# AdaptiveLightingSatellite.net
KiCad netlist of a schematic drawn in Altium Designer
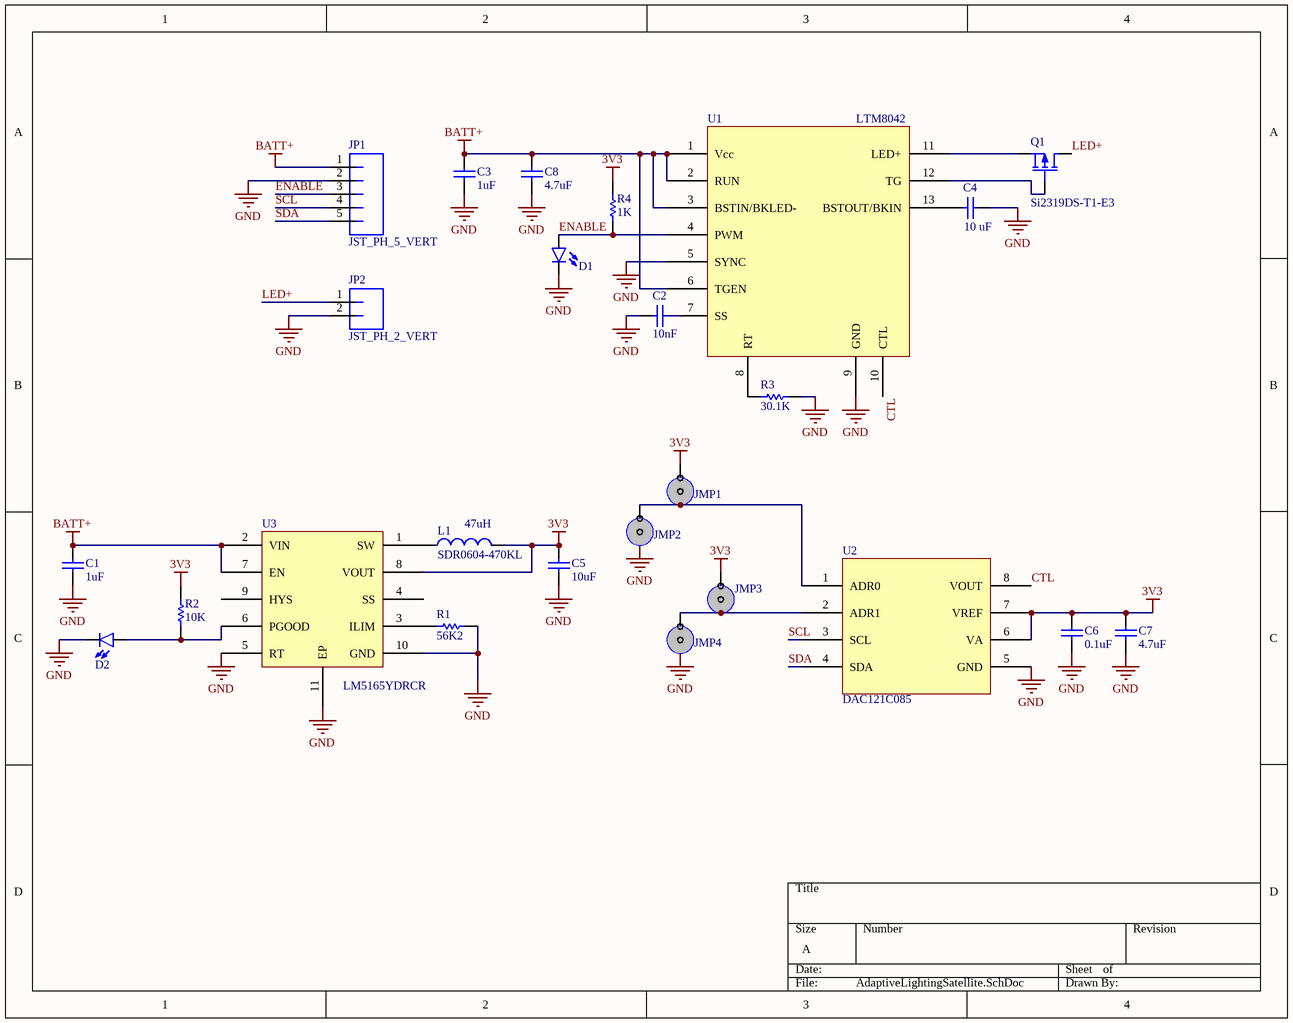
[diagram p0: AdaptiveLightingSatellite.SchDoc]

(export (version "E")
  (design (tool "Eeschema 10.0.6"))
  (components
    (comp (ref "C1")
      (value "1uF")
      (footprint "C0805[2012X120]")
      (description "CAP_1uF 50V 20% 0805 (2012 metric)")
      (fields (field (name "MANUFACTURER") "TDK") (field (name "PARTNUMBER") "C2012X5R1H105M085AB"))
      (libsource (lib "Capacitors") (part "CAP_1uF_100V_0805_20%"))
    )
    (comp (ref "C2")
      (value "10nF")
      (footprint "C0402[1005X55]")
      (description "10nF 100V 10% 0402 (1005 Metric)")
      (fields (field (name "PARTNUMBER") "C1005X7S2A103K050BB") (field (name "MANUFACTURER") "TDK"))
      (libsource (lib "Capacitors") (part "CAP_10nF_100V_0402_10%"))
    )
    (comp (ref "C3")
      (value "1uF")
      (footprint "C0805[2012X120]")
      (description "CAP_1uF 50V 20% 0805 (2012 metric)")
      (fields (field (name "MANUFACTURER") "TDK") (field (name "PARTNUMBER") "C2012X5R1H105M085AB"))
      (libsource (lib "Capacitors") (part "CAP_1uF_100V_0805_20%"))
    )
    (comp (ref "C4")
      (value "10 uF")
      (footprint "C1210[3225X150]")
      (description "10uF 50V X5R +/-20% 1210")
      (fields (field (name "VOLTAGE") "50V") (field (name "MANUFACTURER") "Taiyo Yuden"))
      (libsource (lib "Capacitors") (part "CAP_10uF_50V_1210_20%"))
    )
    (comp (ref "C5")
      (value "10uF")
      (footprint "C0402[1005X55]")
      (description "10uF 6.3V 20% 0402 (1005 Metric)")
      (fields (field (name "PARTNUMBER") "GRM155R60J106ME44D") (field (name "MANUFACTURER") "Murata"))
      (libsource (lib "Capacitors") (part "CAP_10uF_6.3V_0402_20%"))
    )
    (comp (ref "C6")
      (value "0.1uF")
      (footprint "C0402[1005X55]")
      (description "0.1uF 6.3V 10% 0402 (1005 Metric)")
      (fields (field (name "PARTNUMBER") "GRM155R70J104KA01D") (field (name "MANUFACTURER") "Murata"))
      (libsource (lib "Capacitors") (part "CAP_0.1uF_6.3V_0402_10%"))
    )
    (comp (ref "C7")
      (value "4.7uF")
      (footprint "C0402[1005X55]")
      (description "4.7uF 6.3V 20% 0402 (1005 Metric)")
      (fields (field (name "PARTNUMBER") "GRM155R60J475ME47D") (field (name "MANUFACTURER") "Murata"))
      (libsource (lib "Capacitors") (part "CAP_4.7uF_6.3V_0402_20%"))
    )
    (comp (ref "C8")
      (value "4.7uF")
      (footprint "C1210[3225X200]")
      (description "4.7uF 100V 10% 1210 (3225 Metric)")
      (fields (field (name "PARTNUMBER") "GRJ32DC72A475KE11L") (field (name "MANUFACTURER") "Murata"))
      (libsource (lib "Capacitors") (part "CAP_4.7uF_100V_1210_10%"))
    )
    (comp (ref "D1")
      (value "LED_0603_GREEN_5mA")
      (footprint "LED0603")
      (fields (field (name "PARTNUMBER") "LTST-C193TGKT-5A") (field (name "MANUFACTURER") "Lite-On Inc."))
      (libsource (lib "LEDs") (part "LED_0603_GREEN_5mA"))
    )
    (comp (ref "D2")
      (value "LED_0603_BLUE_5mA")
      (footprint "LED0603")
      (fields (field (name "PARTNUMBER") "LTST-C193TBKT-5A") (field (name "MANUFACTURER") "Lite-On Inc."))
      (libsource (lib "LEDs") (part "LED_0603_BLUE_5mA"))
    )
    (comp (ref "JMP1")
      (value "Solder Jumper")
      (footprint "SOLDER-JUMPER")
      (libsource (lib "Connectors") (part "SOLDER_JMPR"))
    )
    (comp (ref "JMP2")
      (value "Solder Jumper")
      (footprint "SOLDER-JUMPER")
      (libsource (lib "Connectors") (part "SOLDER_JMPR"))
    )
    (comp (ref "JMP3")
      (value "~")
      (footprint "SOLDER-JUMPER")
      (libsource (lib "Connectors") (part "SOLDER_JMPR"))
    )
    (comp (ref "JMP4")
      (value "Solder Jumper")
      (footprint "SOLDER-JUMPER")
      (libsource (lib "Connectors") (part "SOLDER_JMPR"))
    )
    (comp (ref "JP1")
      (value "JST_PH_5_VERT")
      (footprint "JST-PH-5-PTH-VERT")
      (fields
        (field (name "MANUFACTURER") "JST Sales America, Inc.")
        (field (name "PARTNUMBER") "B5B-PH-K-S(LF)(SN)")
      )
      (libsource (lib "Connectors") (part "JST_PH_5_VERT"))
    )
    (comp (ref "JP2")
      (value "JST_PH_2_VERT")
      (footprint "JST-PH-2-PTH-VERT")
      (fields
        (field (name "MANUFACTURER") "JST Sales America, Inc.")
        (field (name "PARTNUMBER") "B2B-PH-K-S(LF)(SN)")
      )
      (libsource (lib "Connectors") (part "JST_PH_2_VERT"))
    )
    (comp (ref "L1")
      (value "SDR0604-470KL")
      (footprint "SDR0604")
      (description "47uH 10% 0.72A 0604")
      (fields (field (name "MANUFACTURER") "Bourns") (field (name "ALTIUM_VALUE") "47uH"))
      (libsource (lib "Inductors") (part "SDR0604-470KL"))
    )
    (comp (ref "Q1")
      (value "Si2319DS-T1-E3")
      (footprint "SOT23-3")
      (description "P-Channel MOSFET")
      (fields (field (name "MANUFACTURER") "Vishay") (field (name "PARTNUMBER") "Si2319DS-T1-E3 #PBF"))
      (libsource (lib "MOSFETs") (part "Si2319DS-T1-E3"))
    )
    (comp (ref "R1")
      (value "56K2")
      (footprint "R0402[1005]")
      (description "56K2 0.063W 1% 0402 (1005 Metric)")
      (fields (field (name "MANUFACTURER") "KOA Speer") (field (name "PARTNUMBER") "RK73H1ETTP5622F"))
      (libsource (lib "Resistors") (part "RES_56K2_0402_1%"))
    )
    (comp (ref "R2")
      (value "10K")
      (footprint "R0402[1005]")
      (description "10K 0.063W 1% 0402 (1005 Metric)")
      (fields (field (name "MANUFACTURER") "KOA Speer") (field (name "PARTNUMBER") "RK73H1ETTP1002F"))
      (libsource (lib "Resistors") (part "RES_10K_0402_1%"))
    )
    (comp (ref "R3")
      (value "30.1K")
      (footprint "R0603[1608]")
      (description "30.1K 0.06W 1% 0603 (1005 Metric)")
      (fields (field (name "MANUFACTURER") "NIC Corporation") (field (name "PARTNUMBER") "NRC06F3012TRF"))
      (libsource (lib "Resistors") (part "RES_30.1K_0603_1%"))
    )
    (comp (ref "R4")
      (value "1K")
      (footprint "R0402[1005]")
      (description "1K 0.063W 1% 0402 (1005 Metric)")
      (fields (field (name "MANUFACTURER") "KOA Speer") (field (name "PARTNUMBER") "RK73H1ETTP1001F"))
      (libsource (lib "Resistors") (part "RES_1K_0402_1%"))
    )
    (comp (ref "U1")
      (value "LTM8042")
      (footprint "LGA-77")
      (fields (field (name "MANUFACTURER") "Linear Technology") (field (name "PARTNUMBER") "LTM8042EV#PBF"))
      (libsource (lib "ICs") (part "LTM8042"))
    )
    (comp (ref "U2")
      (value "DAC121C085")
      (footprint "TSSOP-8")
      (description "12 Bit Digital to Analog Converter")
      (fields (field (name "MANUFACTURER") "Texas Instruments"))
      (libsource (lib "ICs") (part "DAC121C085"))
    )
    (comp (ref "U3")
      (value "LM5165YDRCR")
      (footprint "VSON-10 (3mmx3mm)")
      (description "LM5165 3-V to 65-V Input, 150-mA Synchronous Buck Converter")
      (fields (field (name "MANUFACTURER") "Texas Instruments"))
      (libsource (lib "ICs") (part "LM5165YDRCR"))
    )
  )
  (nets
    (net (code "1") (name "/CTL") (class "Default")
      (node (ref "U1") (pin "10") (pinfunction "CTL_10") (pintype "passive"))
      (node (ref "U2") (pin "8") (pinfunction "VOUT_8") (pintype "passive"))
    )
    (net (code "2") (name "/ENABLE") (class "Default")
      (node (ref "D1") (pin "A") (pinfunction "A_A") (pintype "passive"))
      (node (ref "JP1") (pin "3") (pinfunction "3_3") (pintype "passive"))
      (node (ref "R4") (pin "1") (pinfunction "1_1") (pintype "passive"))
      (node (ref "U1") (pin "4") (pinfunction "PWM_4") (pintype "passive"))
    )
    (net (code "3") (name "/LED+") (class "Default")
      (node (ref "JP2") (pin "1") (pinfunction "1_1") (pintype "passive"))
      (node (ref "Q1") (pin "2") (pinfunction "D_2") (pintype "passive"))
    )
    (net (code "4") (name "/SCL") (class "Default")
      (node (ref "JP1") (pin "4") (pinfunction "4_4") (pintype "passive"))
      (node (ref "U2") (pin "3") (pinfunction "SCL_3") (pintype "passive"))
    )
    (net (code "5") (name "/SDA") (class "Default")
      (node (ref "JP1") (pin "5") (pinfunction "5_5") (pintype "passive"))
      (node (ref "U2") (pin "4") (pinfunction "SDA_4") (pintype "passive"))
    )
    (net (code "6") (name "3V3") (class "Default")
      (node (ref "C5") (pin "2") (pinfunction "2_2") (pintype "passive"))
      (node (ref "C6") (pin "1") (pinfunction "1_1") (pintype "passive"))
      (node (ref "C7") (pin "2") (pinfunction "2_2") (pintype "passive"))
      (node (ref "JMP1") (pin "1") (pintype "passive"))
      (node (ref "JMP3") (pin "1") (pintype "passive"))
      (node (ref "L1") (pin "2") (pinfunction "2_2") (pintype "passive"))
      (node (ref "R2") (pin "1") (pinfunction "1_1") (pintype "passive"))
      (node (ref "R4") (pin "2") (pinfunction "2_2") (pintype "passive"))
      (node (ref "U2") (pin "6") (pinfunction "VA_6") (pintype "passive"))
      (node (ref "U2") (pin "7") (pinfunction "VREF_7") (pintype "passive"))
      (node (ref "U3") (pin "8") (pinfunction "VOUT_8") (pintype "passive"))
    )
    (net (code "7") (name "BATT+") (class "Default")
      (node (ref "C1") (pin "2") (pinfunction "2_2") (pintype "passive"))
      (node (ref "C3") (pin "2") (pinfunction "2_2") (pintype "passive"))
      (node (ref "C8") (pin "2") (pinfunction "2_2") (pintype "passive"))
      (node (ref "JP1") (pin "1") (pinfunction "1_1") (pintype "passive"))
      (node (ref "U1") (pin "1") (pinfunction "Vcc_1") (pintype "passive"))
      (node (ref "U1") (pin "2") (pinfunction "RUN_2") (pintype "passive"))
      (node (ref "U1") (pin "3") (pinfunction "BSTIN/BKLED-_3") (pintype "passive"))
      (node (ref "U1") (pin "6") (pinfunction "TGEN_6") (pintype "passive"))
      (node (ref "U3") (pin "2") (pinfunction "VIN_2") (pintype "passive"))
      (node (ref "U3") (pin "7") (pinfunction "EN_7") (pintype "passive"))
    )
    (net (code "8") (name "GND") (class "Default")
      (node (ref "C1") (pin "1") (pinfunction "1_1") (pintype "passive"))
      (node (ref "C2") (pin "1") (pinfunction "1_1") (pintype "passive"))
      (node (ref "C3") (pin "1") (pinfunction "1_1") (pintype "passive"))
      (node (ref "C4") (pin "2") (pinfunction "2_2") (pintype "passive"))
      (node (ref "C5") (pin "1") (pinfunction "1_1") (pintype "passive"))
      (node (ref "C6") (pin "2") (pinfunction "2_2") (pintype "passive"))
      (node (ref "C7") (pin "1") (pinfunction "1_1") (pintype "passive"))
      (node (ref "C8") (pin "1") (pinfunction "1_1") (pintype "passive"))
      (node (ref "D1") (pin "C") (pinfunction "C_C") (pintype "passive"))
      (node (ref "D2") (pin "C") (pinfunction "C_C") (pintype "passive"))
      (node (ref "JMP2") (pin "2") (pinfunction "2_2") (pintype "passive"))
      (node (ref "JMP4") (pin "2") (pinfunction "2_2") (pintype "passive"))
      (node (ref "JP1") (pin "2") (pinfunction "2_2") (pintype "passive"))
      (node (ref "JP2") (pin "2") (pinfunction "2_2") (pintype "passive"))
      (node (ref "R1") (pin "2") (pinfunction "2_2") (pintype "passive"))
      (node (ref "R3") (pin "1") (pinfunction "1_1") (pintype "passive"))
      (node (ref "U1") (pin "5") (pinfunction "SYNC_5") (pintype "passive"))
      (node (ref "U1") (pin "9") (pinfunction "GND_9") (pintype "passive"))
      (node (ref "U2") (pin "5") (pinfunction "GND_5") (pintype "passive"))
      (node (ref "U3") (pin "10") (pinfunction "GND_10") (pintype "passive"))
      (node (ref "U3") (pin "11") (pinfunction "EP_11") (pintype "passive"))
      (node (ref "U3") (pin "5") (pinfunction "RT_5") (pintype "passive"))
    )
    (net (code "9") (name "Net-(Q1-G)") (class "Default")
      (node (ref "Q1") (pin "1") (pinfunction "G_1") (pintype "passive"))
      (node (ref "U1") (pin "12") (pinfunction "TG_12") (pintype "passive"))
    )
    (net (code "10") (name "Net-(Q1-S)") (class "Default")
      (node (ref "Q1") (pin "3") (pinfunction "S_3") (pintype "passive"))
      (node (ref "U1") (pin "11") (pinfunction "LED+_11") (pintype "passive"))
    )
    (net (code "11") (name "Net-(U1-BSTOUT{slash}BKIN)") (class "Default")
      (node (ref "C4") (pin "1") (pinfunction "1_1") (pintype "passive"))
      (node (ref "U1") (pin "13") (pinfunction "BSTOUT/BKIN_13") (pintype "passive"))
    )
    (net (code "12") (name "Net-(U1-RT)") (class "Default")
      (node (ref "R3") (pin "2") (pinfunction "2_2") (pintype "passive"))
      (node (ref "U1") (pin "8") (pinfunction "RT_8") (pintype "passive"))
    )
    (net (code "13") (name "Net-(U1-SS)") (class "Default")
      (node (ref "C2") (pin "2") (pinfunction "2_2") (pintype "passive"))
      (node (ref "U1") (pin "7") (pinfunction "SS_7") (pintype "passive"))
    )
    (net (code "14") (name "Net-(U2-ADR0)") (class "Default")
      (node (ref "JMP1") (pin "2") (pinfunction "2_2") (pintype "passive"))
      (node (ref "JMP2") (pin "1") (pintype "passive"))
      (node (ref "U2") (pin "1") (pinfunction "ADR0_1") (pintype "passive"))
    )
    (net (code "15") (name "Net-(U2-ADR1)") (class "Default")
      (node (ref "JMP3") (pin "2") (pinfunction "2_2") (pintype "passive"))
      (node (ref "JMP4") (pin "1") (pintype "passive"))
      (node (ref "U2") (pin "2") (pinfunction "ADR1_2") (pintype "passive"))
    )
    (net (code "16") (name "Net-(U3-ILIM)") (class "Default")
      (node (ref "R1") (pin "1") (pinfunction "1_1") (pintype "passive"))
      (node (ref "U3") (pin "3") (pinfunction "ILIM_3") (pintype "passive"))
    )
    (net (code "17") (name "Net-(U3-PGOOD)") (class "Default")
      (node (ref "D2") (pin "A") (pinfunction "A_A") (pintype "passive"))
      (node (ref "R2") (pin "2") (pinfunction "2_2") (pintype "passive"))
      (node (ref "U3") (pin "6") (pinfunction "PGOOD_6") (pintype "passive"))
    )
    (net (code "18") (name "Net-(U3-SW)") (class "Default")
      (node (ref "L1") (pin "1") (pinfunction "1_1") (pintype "passive"))
      (node (ref "U3") (pin "1") (pinfunction "SW_1") (pintype "passive"))
    )
    (net (code "19") (name "unconnected-(U3-HYS-Pad9)") (class "Default")
      (node (ref "U3") (pin "9") (pinfunction "HYS_9") (pintype "passive"))
    )
    (net (code "20") (name "unconnected-(U3-SS-Pad4)") (class "Default")
      (node (ref "U3") (pin "4") (pinfunction "SS_4") (pintype "passive"))
    )
  )
)
